# Pulser.net
KiCad netlist of a schematic drawn in Altium Designer
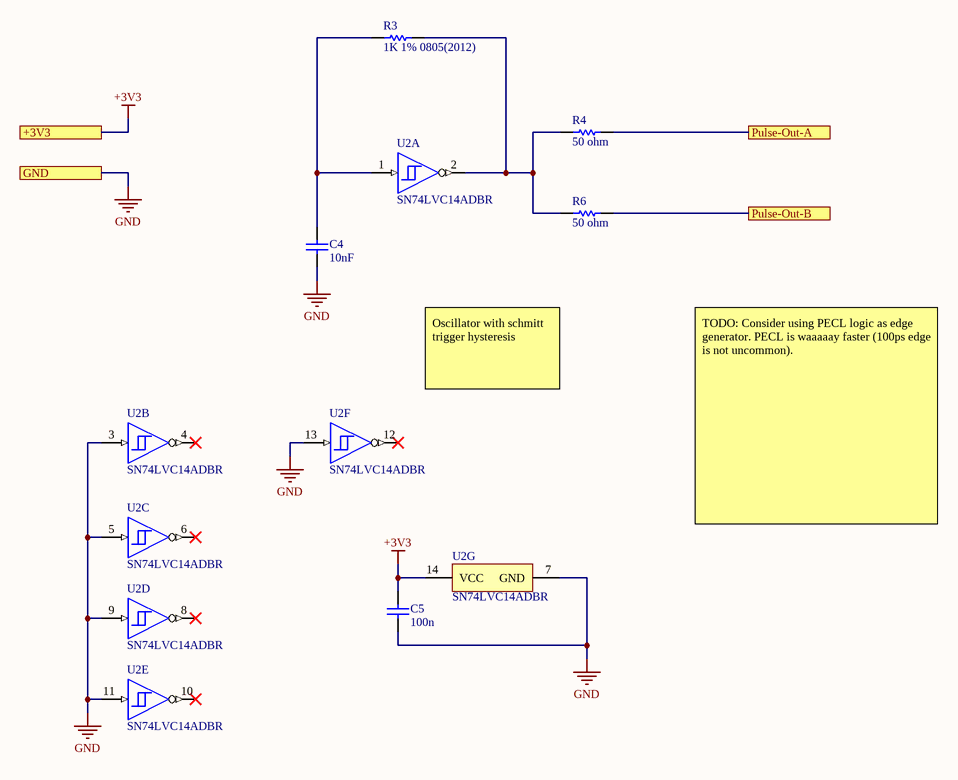
[diagram p0: Pulser.SchDoc]

(export (version "E")
  (design (tool "Eeschema 10.0.6"))
  (components
    (comp (ref "C4")
      (value "10nF")
      (footprint "CAPC2013X88X50LL20T25")
      (fields (field (name "PART NUMBER") "C0805C103J3GACTU") (field (name "MANUFACTURER") "Kemet"))
      (libsource (lib "Altium Content Vault") (part "CAP"))
    )
    (comp (ref "C5")
      (value "100n")
      (footprint "CAPC2013X88X50NL20T25")
      (fields (field (name "PART NUMBER") "C0805C104K5RACTU") (field (name "MANUFACTURER") "Kemet"))
      (libsource (lib "Altium Content Vault") (part "CAP"))
    )
    (comp (ref "R3")
      (value "1K 1% 0805(2012)")
      (footprint "RESC0805(2012)_M")
      (description "1K 0.125W 1% 0805 (2012 Metric)  SMD")
      (fields (field (name "TOLERANCE") "1 %") (field (name "POWER") "0.125 W"))
      (libsource (lib "Altium Content Vault") (part "RES"))
    )
    (comp (ref "R4")
      (value "50 ohm")
      (footprint "RESC1609X50X30NL10T20")
      (fields (field (name "PART NUMBER") "CRCW060350R0FKEA") (field (name "MANUFACTURER") "Vishay Dale"))
      (libsource (lib "Altium Content Vault") (part "RES"))
    )
    (comp (ref "R6")
      (value "50 ohm")
      (footprint "RESC1609X50X30NL10T20")
      (fields (field (name "PART NUMBER") "CRCW060350R0FKEA") (field (name "MANUFACTURER") "Vishay Dale"))
      (libsource (lib "Altium Content Vault") (part "RES"))
    )
    (comp (ref "U2")
      (value "SN74LVC14ADBR")
      (footprint "DB0014A_M")
      (description "Hex Schmitt-Trigger Inverter, DB0014A, LARGE T&R")
      (fields
        (field (name "GENERIC PART NUMBER") "SN74LVC14A")
        (field (name "MANUFACTURER") "Texas Instruments")
      )
      (libsource (lib "Altium Content Vault") (part "TI-CD_SNX4XXXXXX4X_19A-14-SCHMITT"))
    )
  )
  (nets
    (net (code "1") (name "+3V3") (class "Default")
      (node (ref "C5") (pin "2") (pinfunction "2_2") (pintype "passive"))
      (node (ref "U2") (pin "14") (pinfunction "VCC_14") (pintype "power_in"))
    )
    (net (code "2") (name "/Pulse-Out-A") (class "Default")
      (node (ref "R4") (pin "2") (pinfunction "2_2") (pintype "passive"))
    )
    (net (code "3") (name "/Pulse-Out-B") (class "Default")
      (node (ref "R6") (pin "2") (pinfunction "2_2") (pintype "passive"))
    )
    (net (code "4") (name "GND") (class "Default")
      (node (ref "C4") (pin "1") (pinfunction "1_1") (pintype "passive"))
      (node (ref "C5") (pin "1") (pinfunction "1_1") (pintype "passive"))
      (node (ref "U2") (pin "11") (pinfunction "5A_11") (pintype "input"))
      (node (ref "U2") (pin "13") (pinfunction "6A_13") (pintype "input"))
      (node (ref "U2") (pin "3") (pinfunction "2A_3") (pintype "input"))
      (node (ref "U2") (pin "5") (pinfunction "3A_5") (pintype "input"))
      (node (ref "U2") (pin "7") (pinfunction "GND_7") (pintype "power_in"))
      (node (ref "U2") (pin "9") (pinfunction "4A_9") (pintype "input"))
    )
    (net (code "5") (name "Net-(U2A-1A)") (class "Default")
      (node (ref "C4") (pin "2") (pinfunction "2_2") (pintype "passive"))
      (node (ref "R3") (pin "1") (pinfunction "1_1") (pintype "passive"))
      (node (ref "U2") (pin "1") (pinfunction "1A_1") (pintype "input"))
    )
    (net (code "6") (name "Net-(U2A-~{1Y})") (class "Default")
      (node (ref "R3") (pin "2") (pinfunction "2_2") (pintype "passive"))
      (node (ref "R4") (pin "1") (pinfunction "1_1") (pintype "passive"))
      (node (ref "R6") (pin "1") (pinfunction "1_1") (pintype "passive"))
      (node (ref "U2") (pin "2") (pinfunction "~{1Y}_2") (pintype "output"))
    )
    (net (code "7") (name "unconnected-(U2B-~{2Y}-Pad4)") (class "Default")
      (node (ref "U2") (pin "4") (pinfunction "~{2Y}_4") (pintype "output+no_connect"))
    )
    (net (code "8") (name "unconnected-(U2C-~{3Y}-Pad6)") (class "Default")
      (node (ref "U2") (pin "6") (pinfunction "~{3Y}_6") (pintype "output+no_connect"))
    )
    (net (code "9") (name "unconnected-(U2D-~{4Y}-Pad8)") (class "Default")
      (node (ref "U2") (pin "8") (pinfunction "~{4Y}_8") (pintype "output+no_connect"))
    )
    (net (code "10") (name "unconnected-(U2E-~{5Y}-Pad10)") (class "Default")
      (node (ref "U2") (pin "10") (pinfunction "~{5Y}_10") (pintype "output+no_connect"))
    )
    (net (code "11") (name "unconnected-(U2F-~{6Y}-Pad12)") (class "Default")
      (node (ref "U2") (pin "12") (pinfunction "~{6Y}_12") (pintype "output+no_connect"))
    )
  )
)
